# main.net
KiCad netlist of a schematic drawn in EAGLE
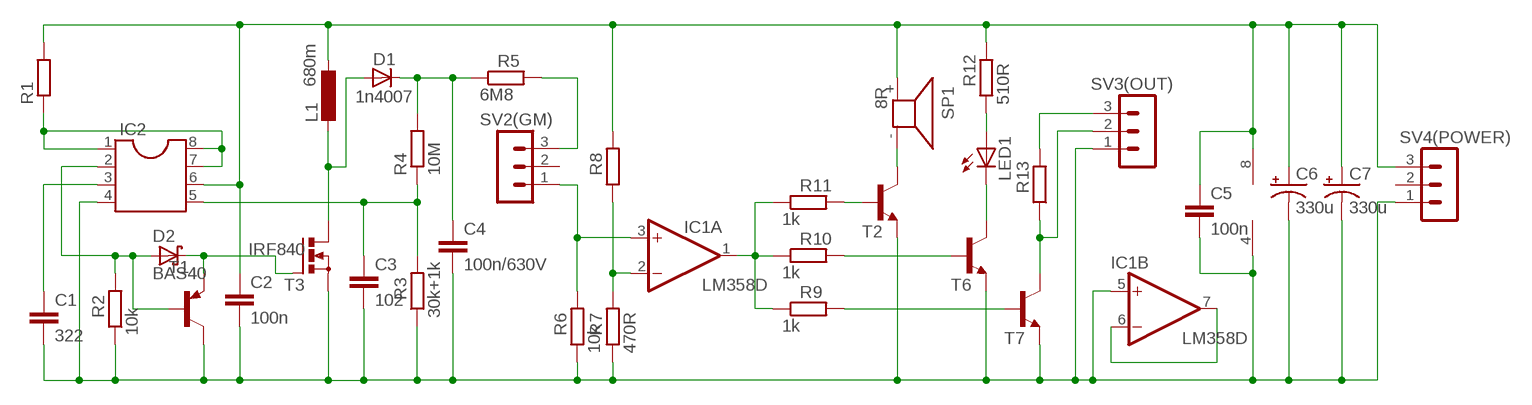
[diagram p0: schematic, sheet 1]

(export (version "E")
  (design (tool "Eeschema 10.0.6"))
  (components
    (comp (ref "C1")
      (value "322")
      (footprint "eagle-import:C050-025X075")
      (libsource (lib "eagle-import") (part "C-EU050-025X075"))
    )
    (comp (ref "C2")
      (value "100n")
      (footprint "eagle-import:C3216")
      (libsource (lib "eagle-import") (part "C-EUC3216"))
    )
    (comp (ref "C3")
      (value "102")
      (footprint "eagle-import:C050-025X075")
      (libsource (lib "eagle-import") (part "C-EU050-025X075"))
    )
    (comp (ref "C4")
      (value "100n/630V")
      (footprint "eagle-import:C102-064X133")
      (libsource (lib "eagle-import") (part "C-EU102-064X133"))
    )
    (comp (ref "C5")
      (value "100n")
      (footprint "eagle-import:C3216")
      (libsource (lib "eagle-import") (part "C-EUC3216"))
    )
    (comp (ref "C6")
      (value "330u")
      (footprint "eagle-import:A_3216-18W")
      (libsource (lib "eagle-import") (part "CPOL-USA/3216-18W"))
    )
    (comp (ref "C7")
      (value "330u")
      (footprint "eagle-import:A_3216-18W")
      (libsource (lib "eagle-import") (part "CPOL-USA/3216-18W"))
    )
    (comp (ref "D1")
      (value "1n4007")
      (footprint "eagle-import:DO41-10")
      (libsource (lib "eagle-import") (part "1N4004"))
    )
    (comp (ref "D2")
      (value "BAS40")
      (footprint "eagle-import:SOT23")
      (libsource (lib "eagle-import") (part "BAS40"))
    )
    (comp (ref "IC1")
      (value "LM358D")
      (footprint "eagle-import:SO08")
      (libsource (lib "eagle-import") (part "LM358D"))
    )
    (comp (ref "IC2")
      (value "DIL8")
      (footprint "eagle-import:DIL08")
      (libsource (lib "eagle-import") (part "DIL8"))
    )
    (comp (ref "L1")
      (value "680m")
      (footprint "eagle-import:0207_5V")
      (libsource (lib "eagle-import") (part "L-EU0207/5V"))
    )
    (comp (ref "LED1")
      (value "LEDSFH482")
      (footprint "eagle-import:SFH482")
      (libsource (lib "eagle-import") (part "LEDSFH482"))
    )
    (comp (ref "R1")
      (value "R-EU_0207/5V")
      (footprint "eagle-import:0207_5V")
      (libsource (lib "eagle-import") (part "R-EU_0207/5V"))
    )
    (comp (ref "R2")
      (value "10k")
      (footprint "eagle-import:0207_5V")
      (libsource (lib "eagle-import") (part "R-EU_0207/5V"))
    )
    (comp (ref "R3")
      (value "30k+1k")
      (footprint "eagle-import:0207_5V")
      (libsource (lib "eagle-import") (part "R-EU_0207/5V"))
    )
    (comp (ref "R4")
      (value "10M")
      (footprint "eagle-import:0207_5V")
      (libsource (lib "eagle-import") (part "R-EU_0207/5V"))
    )
    (comp (ref "R5")
      (value "6M8")
      (footprint "eagle-import:0207_12")
      (libsource (lib "eagle-import") (part "R-EU_0207/12"))
    )
    (comp (ref "R6")
      (value "10k")
      (footprint "eagle-import:0207_5V")
      (libsource (lib "eagle-import") (part "R-EU_0207/5V"))
    )
    (comp (ref "R7")
      (value "470R")
      (footprint "eagle-import:0207_5V")
      (libsource (lib "eagle-import") (part "R-EU_0207/5V"))
    )
    (comp (ref "R8")
      (value "R-EU_0207/5V")
      (footprint "eagle-import:0207_5V")
      (libsource (lib "eagle-import") (part "R-EU_0207/5V"))
    )
    (comp (ref "R9")
      (value "1k")
      (footprint "eagle-import:M1206")
      (libsource (lib "eagle-import") (part "R-EU_M1206"))
    )
    (comp (ref "R10")
      (value "1k")
      (footprint "eagle-import:M1206")
      (libsource (lib "eagle-import") (part "R-EU_M1206"))
    )
    (comp (ref "R11")
      (value "1k")
      (footprint "eagle-import:M1206")
      (libsource (lib "eagle-import") (part "R-EU_M1206"))
    )
    (comp (ref "R12")
      (value "510R")
      (footprint "eagle-import:M1206")
      (libsource (lib "eagle-import") (part "R-EU_M1206"))
    )
    (comp (ref "R13")
      (value "R-EU_M1206")
      (footprint "eagle-import:M1206")
      (libsource (lib "eagle-import") (part "R-EU_M1206"))
    )
    (comp (ref "SP1")
      (value "8R")
      (footprint "eagle-import:KSS1201")
      (libsource (lib "eagle-import") (part "KSS1201"))
    )
    (comp (ref "SV2(GM)")
      (value "MA03-1")
      (footprint "eagle-import:MA03-1")
      (libsource (lib "eagle-import") (part "MA03-1"))
    )
    (comp (ref "SV3(OUT)")
      (value "MA03-1")
      (footprint "eagle-import:MA03-1")
      (libsource (lib "eagle-import") (part "MA03-1"))
    )
    (comp (ref "SV4(POWER)")
      (value "MA03-1")
      (footprint "eagle-import:MA03-1")
      (libsource (lib "eagle-import") (part "MA03-1"))
    )
    (comp (ref "T1")
      (value "BC807-40-PNP-SOT23-BEC")
      (footprint "eagle-import:SOT23-BEC")
      (libsource (lib "eagle-import") (part "-PNP-SOT23-BECBC807-40"))
    )
    (comp (ref "T2")
      (value "BC848ALT1SMD")
      (footprint "eagle-import:SOT23")
      (libsource (lib "eagle-import") (part "BC848SMDALT1"))
    )
    (comp (ref "T3")
      (value "IRF840")
      (footprint "eagle-import:TO220BV")
      (libsource (lib "eagle-import") (part "BUZ11BV"))
    )
    (comp (ref "T6")
      (value "BC848ALT1SMD")
      (footprint "eagle-import:SOT23")
      (libsource (lib "eagle-import") (part "BC848SMDALT1"))
    )
    (comp (ref "T7")
      (value "BC848ALT1SMD")
      (footprint "eagle-import:SOT23")
      (libsource (lib "eagle-import") (part "BC848SMDALT1"))
    )
  )
  (nets
    (net (code "1") (name "Net-(C1-Pad1)") (class "Default")
      (node (ref "C1") (pin "1") (pinfunction "1_1") (pintype "passive"))
      (node (ref "IC2") (pin "3") (pinfunction "3_3") (pintype "passive"))
    )
    (net (code "2") (name "Net-(C3-Pad1)") (class "Default")
      (node (ref "C3") (pin "1") (pinfunction "1_1") (pintype "passive"))
      (node (ref "IC2") (pin "5") (pinfunction "5_5") (pintype "passive"))
      (node (ref "R3") (pin "2") (pinfunction "2_2") (pintype "passive"))
      (node (ref "R4") (pin "1") (pinfunction "1_1") (pintype "passive"))
    )
    (net (code "3") (name "Net-(C4-Pad1)") (class "Default")
      (node (ref "C4") (pin "1") (pinfunction "1_1") (pintype "passive"))
      (node (ref "D1") (pin "C") (pinfunction "C_C") (pintype "passive"))
      (node (ref "R4") (pin "2") (pinfunction "2_2") (pintype "passive"))
      (node (ref "R5") (pin "1") (pinfunction "1_1") (pintype "passive"))
    )
    (net (code "4") (name "Net-(D1-PadA)") (class "Default")
      (node (ref "D1") (pin "A") (pinfunction "A_A") (pintype "passive"))
      (node (ref "L1") (pin "2") (pinfunction "2_2") (pintype "passive"))
      (node (ref "T3") (pin "D") (pinfunction "D_D") (pintype "passive"))
    )
    (net (code "5") (name "Net-(D2-A)") (class "Default")
      (node (ref "D2") (pin "1") (pinfunction "A_1") (pintype "passive"))
      (node (ref "IC2") (pin "2") (pinfunction "2_2") (pintype "passive"))
      (node (ref "R2") (pin "2") (pinfunction "2_2") (pintype "passive"))
      (node (ref "T1") (pin "B") (pinfunction "B_B") (pintype "passive"))
    )
    (net (code "6") (name "Net-(D2-C)") (class "Default")
      (node (ref "D2") (pin "3") (pinfunction "C_3") (pintype "passive"))
      (node (ref "T1") (pin "E") (pinfunction "E_E") (pintype "passive"))
      (node (ref "T3") (pin "G") (pinfunction "G_G") (pintype "passive"))
    )
    (net (code "7") (name "Net-(IC1A-+IN)") (class "Default")
      (node (ref "IC1") (pin "3") (pinfunction "+IN_3") (pintype "input"))
      (node (ref "R6") (pin "2") (pinfunction "2_2") (pintype "passive"))
      (node (ref "SV2(GM)") (pin "1") (pinfunction "1_1") (pintype "passive"))
    )
    (net (code "8") (name "Net-(IC1A--IN)") (class "Default")
      (node (ref "IC1") (pin "2") (pinfunction "-IN_2") (pintype "input"))
      (node (ref "R7") (pin "2") (pinfunction "2_2") (pintype "passive"))
      (node (ref "R8") (pin "1") (pinfunction "1_1") (pintype "passive"))
    )
    (net (code "9") (name "Net-(IC1A-OUT)") (class "Default")
      (node (ref "IC1") (pin "1") (pinfunction "OUT_1") (pintype "output"))
      (node (ref "R10") (pin "1") (pinfunction "1_1") (pintype "passive"))
      (node (ref "R11") (pin "1") (pinfunction "1_1") (pintype "passive"))
      (node (ref "R9") (pin "1") (pinfunction "1_1") (pintype "passive"))
    )
    (net (code "10") (name "Net-(IC1B-+IN)") (class "Default")
      (node (ref "C1") (pin "2") (pinfunction "2_2") (pintype "passive"))
      (node (ref "C2") (pin "2") (pinfunction "2_2") (pintype "passive"))
      (node (ref "C3") (pin "2") (pinfunction "2_2") (pintype "passive"))
      (node (ref "C4") (pin "2") (pinfunction "2_2") (pintype "passive"))
      (node (ref "C5") (pin "2") (pinfunction "2_2") (pintype "passive"))
      (node (ref "C6") (pin "-") (pinfunction "-_-") (pintype "passive"))
      (node (ref "C7") (pin "-") (pinfunction "-_-") (pintype "passive"))
      (node (ref "IC1") (pin "4") (pinfunction "V-_4") (pintype "power_in"))
      (node (ref "IC1") (pin "5") (pinfunction "+IN_5") (pintype "input"))
      (node (ref "IC2") (pin "4") (pinfunction "4_4") (pintype "passive"))
      (node (ref "R2") (pin "1") (pinfunction "1_1") (pintype "passive"))
      (node (ref "R3") (pin "1") (pinfunction "1_1") (pintype "passive"))
      (node (ref "R6") (pin "1") (pinfunction "1_1") (pintype "passive"))
      (node (ref "R7") (pin "1") (pinfunction "1_1") (pintype "passive"))
      (node (ref "SV3(OUT)") (pin "1") (pinfunction "1_1") (pintype "passive"))
      (node (ref "SV4(POWER)") (pin "1") (pinfunction "1_1") (pintype "passive"))
      (node (ref "T1") (pin "C") (pinfunction "C_C") (pintype "passive"))
      (node (ref "T2") (pin "2") (pinfunction "E_2") (pintype "passive"))
      (node (ref "T3") (pin "S") (pinfunction "S_S") (pintype "passive"))
      (node (ref "T6") (pin "2") (pinfunction "E_2") (pintype "passive"))
      (node (ref "T7") (pin "2") (pinfunction "E_2") (pintype "passive"))
    )
    (net (code "11") (name "Net-(IC1B--IN)") (class "Default")
      (node (ref "IC1") (pin "6") (pinfunction "-IN_6") (pintype "input"))
      (node (ref "IC1") (pin "7") (pinfunction "OUT_7") (pintype "output"))
    )
    (net (code "12") (name "Net-(IC1C-V+)") (class "Default")
      (node (ref "C2") (pin "1") (pinfunction "1_1") (pintype "passive"))
      (node (ref "C5") (pin "1") (pinfunction "1_1") (pintype "passive"))
      (node (ref "C6") (pin "+") (pinfunction "+_+") (pintype "passive"))
      (node (ref "C7") (pin "+") (pinfunction "+_+") (pintype "passive"))
      (node (ref "IC1") (pin "8") (pinfunction "V+_8") (pintype "power_in"))
      (node (ref "IC2") (pin "6") (pinfunction "6_6") (pintype "passive"))
      (node (ref "L1") (pin "1") (pinfunction "1_1") (pintype "passive"))
      (node (ref "R1") (pin "2") (pinfunction "2_2") (pintype "passive"))
      (node (ref "R12") (pin "2") (pinfunction "2_2") (pintype "passive"))
      (node (ref "R8") (pin "2") (pinfunction "2_2") (pintype "passive"))
      (node (ref "SP1") (pin "+") (pinfunction "1_+") (pintype "passive"))
      (node (ref "SV4(POWER)") (pin "3") (pinfunction "3_3") (pintype "passive"))
    )
    (net (code "13") (name "Net-(IC2-Pad1)") (class "Default")
      (node (ref "IC2") (pin "1") (pinfunction "1_1") (pintype "passive"))
      (node (ref "IC2") (pin "7") (pinfunction "7_7") (pintype "passive"))
      (node (ref "IC2") (pin "8") (pinfunction "8_8") (pintype "passive"))
      (node (ref "R1") (pin "1") (pinfunction "1_1") (pintype "passive"))
    )
    (net (code "14") (name "Net-(LED1-C)") (class "Default")
      (node (ref "LED1") (pin "K") (pinfunction "C_K") (pintype "passive"))
      (node (ref "T6") (pin "3") (pinfunction "C_3") (pintype "passive"))
    )
    (net (code "15") (name "Net-(LED1-PadA)") (class "Default")
      (node (ref "LED1") (pin "A") (pinfunction "A_A") (pintype "passive"))
      (node (ref "R12") (pin "1") (pinfunction "1_1") (pintype "passive"))
    )
    (net (code "16") (name "Net-(R5-Pad2)") (class "Default")
      (node (ref "R5") (pin "2") (pinfunction "2_2") (pintype "passive"))
      (node (ref "SV2(GM)") (pin "3") (pinfunction "3_3") (pintype "passive"))
    )
    (net (code "17") (name "Net-(R13-Pad2)") (class "Default")
      (node (ref "R13") (pin "2") (pinfunction "2_2") (pintype "passive"))
      (node (ref "SV3(OUT)") (pin "3") (pinfunction "3_3") (pintype "passive"))
    )
    (net (code "18") (name "Net-(SP1-2)") (class "Default")
      (node (ref "SP1") (pin "-") (pinfunction "2_-") (pintype "passive"))
      (node (ref "T2") (pin "3") (pinfunction "C_3") (pintype "passive"))
    )
    (net (code "19") (name "Net-(T2-B)") (class "Default")
      (node (ref "R11") (pin "2") (pinfunction "2_2") (pintype "passive"))
      (node (ref "T2") (pin "1") (pinfunction "B_1") (pintype "passive"))
    )
    (net (code "20") (name "Net-(T6-B)") (class "Default")
      (node (ref "R10") (pin "2") (pinfunction "2_2") (pintype "passive"))
      (node (ref "T6") (pin "1") (pinfunction "B_1") (pintype "passive"))
    )
    (net (code "21") (name "Net-(T7-B)") (class "Default")
      (node (ref "R9") (pin "2") (pinfunction "2_2") (pintype "passive"))
      (node (ref "T7") (pin "1") (pinfunction "B_1") (pintype "passive"))
    )
    (net (code "22") (name "Net-(T7-C)") (class "Default")
      (node (ref "R13") (pin "1") (pinfunction "1_1") (pintype "passive"))
      (node (ref "SV3(OUT)") (pin "2") (pinfunction "2_2") (pintype "passive"))
      (node (ref "T7") (pin "3") (pinfunction "C_3") (pintype "passive"))
    )
    (net (code "23") (name "unconnected-(SV2(GM)-Pad2)") (class "Default")
      (node (ref "SV2(GM)") (pin "2") (pinfunction "2_2") (pintype "passive"))
    )
    (net (code "24") (name "unconnected-(SV4(POWER)-Pad2)") (class "Default")
      (node (ref "SV4(POWER)") (pin "2") (pinfunction "2_2") (pintype "passive"))
    )
  )
)
